# Rumble.net
KiCad netlist of a schematic drawn in Altium Designer
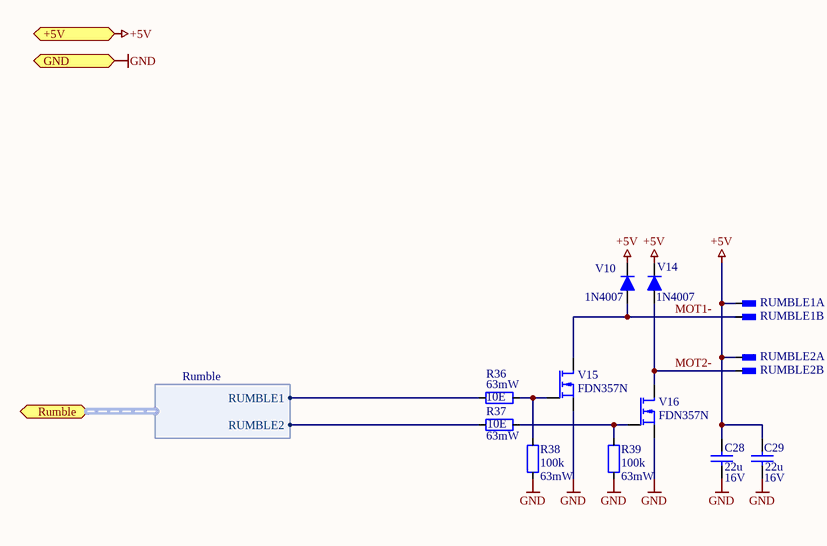
[diagram p0: Rumble.SchDoc]

(export (version "E")
  (design (tool "Eeschema 10.0.6"))
  (components
    (comp (ref "C28")
      (value "22u")
      (footprint "SMD_CAP_0805")
      (description "22µF ±10% 16V Ceramic Capacitor X5R 0805 (2012 Metric)")
      (fields (field (name "VALUE2") "16V") (field (name "Comment") "C_SMD_CER_22U_16V_10%_X5R_0805"))
      (libsource (lib "AM") (part "C_SMD_CER_22U_16V_10%_X5R_0805"))
    )
    (comp (ref "C29")
      (value "22u")
      (footprint "SMD_CAP_0805")
      (description "22µF ±10% 16V Ceramic Capacitor X5R 0805 (2012 Metric)")
      (fields (field (name "VALUE2") "16V") (field (name "Comment") "C_SMD_CER_22U_16V_10%_X5R_0805"))
      (libsource (lib "AM") (part "C_SMD_CER_22U_16V_10%_X5R_0805"))
    )
    (comp (ref "R36")
      (value "10E")
      (footprint "SMD_RES_0402")
      (description "10 Ohms ±0.5% 0.063W, 1/16W Chip Resistor 0402 (1005 Metric) Thin Film")
      (fields
        (field (name "VALUE2") "63mW")
        (field (name "Comment") "R_SMD_THINFILM_10E_0W063_0%5_50PPM_0402")
      )
      (libsource (lib "AM") (part "R_SMD_THINFILM_10E_0W063_0%5_50PPM_0402"))
    )
    (comp (ref "R37")
      (value "10E")
      (footprint "SMD_RES_0402")
      (description "10 Ohms ±0.5% 0.063W, 1/16W Chip Resistor 0402 (1005 Metric) Thin Film")
      (fields
        (field (name "VALUE2") "63mW")
        (field (name "Comment") "R_SMD_THINFILM_10E_0W063_0%5_50PPM_0402")
      )
      (libsource (lib "AM") (part "R_SMD_THINFILM_10E_0W063_0%5_50PPM_0402"))
    )
    (comp (ref "R38")
      (value "100k")
      (footprint "SMD_RES_0402")
      (description "100 kOhms ±1% 0.063W, 1/16W Chip Resistor 0402 (1005 Metric) Thin Film")
      (fields
        (field (name "VALUE2") "63mW")
        (field (name "Comment") "R_SMD_THINFILM_100K_0W063_1%_50PPM_0402")
      )
      (libsource (lib "AM") (part "R_SMD_THINFILM_100K_0W063_1%_50PPM_0402"))
    )
    (comp (ref "R39")
      (value "100k")
      (footprint "SMD_RES_0402")
      (description "100 kOhms ±1% 0.063W, 1/16W Chip Resistor 0402 (1005 Metric) Thin Film")
      (fields
        (field (name "VALUE2") "63mW")
        (field (name "Comment") "R_SMD_THINFILM_100K_0W063_1%_50PPM_0402")
      )
      (libsource (lib "AM") (part "R_SMD_THINFILM_100K_0W063_1%_50PPM_0402"))
    )
    (comp (ref "RUMBLE1")
      (value "X_CONNECTOR_P2.54_D0.9_1X2")
      (footprint "THT_CON_P2.54_D0.9_1X2")
      (description "Pitch 2.54, Diameter 0.9mm, 1 row, 2 columns")
      (libsource (lib "AM") (part "X_CONNECTOR_P2.54_D0.9_1X2"))
    )
    (comp (ref "RUMBLE2")
      (value "X_CONNECTOR_P2.54_D0.9_1X2")
      (footprint "THT_CON_P2.54_D0.9_1X2")
      (description "Pitch 2.54, Diameter 0.9mm, 1 row, 2 columns")
      (libsource (lib "AM") (part "X_CONNECTOR_P2.54_D0.9_1X2"))
    )
    (comp (ref "V10")
      (value "V_SMD_DIODE_1N4007_SODFL-123")
      (footprint "SMD_SODFL_123")
      (description "Diode Standard 1000V 1A Surface Mount SOD-123FL")
      (fields (field (name "TYPE") "1N4007"))
      (libsource (lib "AM") (part "V_SMD_DIODE_1N4007_SODFL-123"))
    )
    (comp (ref "V14")
      (value "V_SMD_DIODE_1N4007_SODFL-123")
      (footprint "SMD_SODFL_123")
      (description "Diode Standard 1000V 1A Surface Mount SOD-123FL")
      (fields (field (name "TYPE") "1N4007"))
      (libsource (lib "AM") (part "V_SMD_DIODE_1N4007_SODFL-123"))
    )
    (comp (ref "V15")
      (value "V_SMD_FET_NMOS_FDN357N_30V_1A9_4NC2_0W5_SOT-23-3")
      (footprint "SMD_SOT_23_3")
      (description "N-Channel Logic Level Enhancement Mode Field Effect Transistor")
      (fields (field (name "TYPE") "FDN357N"))
      (libsource (lib "AM") (part "V_SMD_FET_NMOS_FDN357N_30V_1A9_4NC2_0W5_SOT-23-3"))
    )
    (comp (ref "V16")
      (value "V_SMD_FET_NMOS_FDN357N_30V_1A9_4NC2_0W5_SOT-23-3")
      (footprint "SMD_SOT_23_3")
      (description "N-Channel Logic Level Enhancement Mode Field Effect Transistor")
      (fields (field (name "TYPE") "FDN357N"))
      (libsource (lib "AM") (part "V_SMD_FET_NMOS_FDN357N_30V_1A9_4NC2_0W5_SOT-23-3"))
    )
  )
  (nets
    (net (code "2") (name "+5V") (class "Default")
      (node (ref "C28") (pin "2") (pinfunction "2_2") (pintype "passive"))
      (node (ref "C29") (pin "2") (pinfunction "2_2") (pintype "passive"))
      (node (ref "RUMBLE1") (pin "1") (pinfunction "1_1") (pintype "passive"))
      (node (ref "RUMBLE2") (pin "1") (pinfunction "1_1") (pintype "passive"))
      (node (ref "V10") (pin "2") (pinfunction "2_2") (pintype "passive"))
      (node (ref "V14") (pin "2") (pinfunction "2_2") (pintype "passive"))
    )
    (net (code "3") (name "/MOT1-") (class "Default")
      (node (ref "RUMBLE1") (pin "2") (pinfunction "2_2") (pintype "passive"))
      (node (ref "V10") (pin "1") (pinfunction "1_1") (pintype "passive"))
      (node (ref "V15") (pin "3") (pinfunction "Drain_3") (pintype "passive"))
    )
    (net (code "4") (name "/MOT2-") (class "Default")
      (node (ref "RUMBLE2") (pin "2") (pinfunction "2_2") (pintype "passive"))
      (node (ref "V14") (pin "1") (pinfunction "1_1") (pintype "passive"))
      (node (ref "V16") (pin "3") (pinfunction "Drain_3") (pintype "passive"))
    )
    (net (code "5") (name "/RUMBLE1") (class "Default")
      (node (ref "R36") (pin "1") (pinfunction "1_1") (pintype "passive"))
    )
    (net (code "6") (name "/RUMBLE2") (class "Default")
      (node (ref "R37") (pin "1") (pinfunction "1_1") (pintype "passive"))
    )
    (net (code "8") (name "GND") (class "Default")
      (node (ref "C28") (pin "1") (pinfunction "1_1") (pintype "passive"))
      (node (ref "C29") (pin "1") (pinfunction "1_1") (pintype "passive"))
      (node (ref "R38") (pin "1") (pinfunction "1_1") (pintype "passive"))
      (node (ref "R39") (pin "1") (pinfunction "1_1") (pintype "passive"))
      (node (ref "V15") (pin "2") (pinfunction "Source_2") (pintype "passive"))
      (node (ref "V16") (pin "2") (pinfunction "Source_2") (pintype "passive"))
    )
    (net (code "9") (name "Net-(V15-Gate)") (class "Default")
      (node (ref "R36") (pin "2") (pinfunction "2_2") (pintype "passive"))
      (node (ref "R38") (pin "2") (pinfunction "2_2") (pintype "passive"))
      (node (ref "V15") (pin "1") (pinfunction "Gate_1") (pintype "passive"))
    )
    (net (code "10") (name "Net-(V16-Gate)") (class "Default")
      (node (ref "R37") (pin "2") (pinfunction "2_2") (pintype "passive"))
      (node (ref "R39") (pin "2") (pinfunction "2_2") (pintype "passive"))
      (node (ref "V16") (pin "1") (pinfunction "Gate_1") (pintype "passive"))
    )
  )
)
